# Key_Pull-Up.net
KiCad netlist of a schematic drawn in Altium Designer
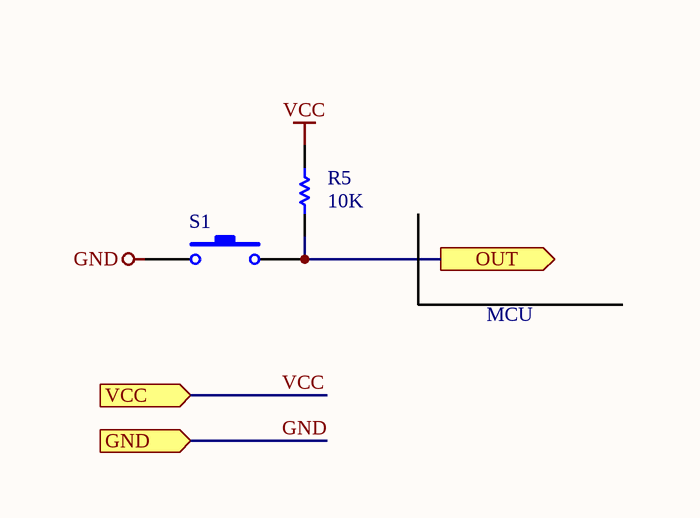
[diagram p0: Key_Pull-Up.SchDoc]

(export (version "E")
  (design (tool "Eeschema 10.0.6"))
  (components
    (comp (ref "R5")
      (value "10K")
      (footprint "AXIAL-0.4")
      (description "Resistor")
      (fields
        (field (name "MANUFACTURER") "Generic Components")
        (field (name "Comment") "Res1")
        (field (name "PUBLISHER") "Altium Limited")
      )
      (libsource (lib "Miscellaneous Devices") (part "Res1"))
    )
    (comp (ref "S1")
      (value "SW-PB")
      (footprint "SPST-2_2")
      (description "Switch")
      (fields (field (name "MANUFACTURER") "Generic Components") (field (name "PUBLISHER") "Altium Limited"))
      (libsource (lib "Miscellaneous Devices") (part "SW-PB"))
    )
  )
  (nets
    (net (code "1") (name "/OUT") (class "Default")
      (node (ref "R5") (pin "2") (pinfunction "2_2") (pintype "passive"))
      (node (ref "S1") (pin "2") (pinfunction "2_2") (pintype "passive"))
    )
    (net (code "2") (name "GND") (class "Default")
      (node (ref "S1") (pin "1") (pinfunction "1_1") (pintype "passive"))
    )
    (net (code "3") (name "VCC") (class "Default")
      (node (ref "R5") (pin "1") (pinfunction "1_1") (pintype "passive"))
    )
  )
)
